# diy-ltcc.net
KiCad netlist of a schematic drawn in EAGLE
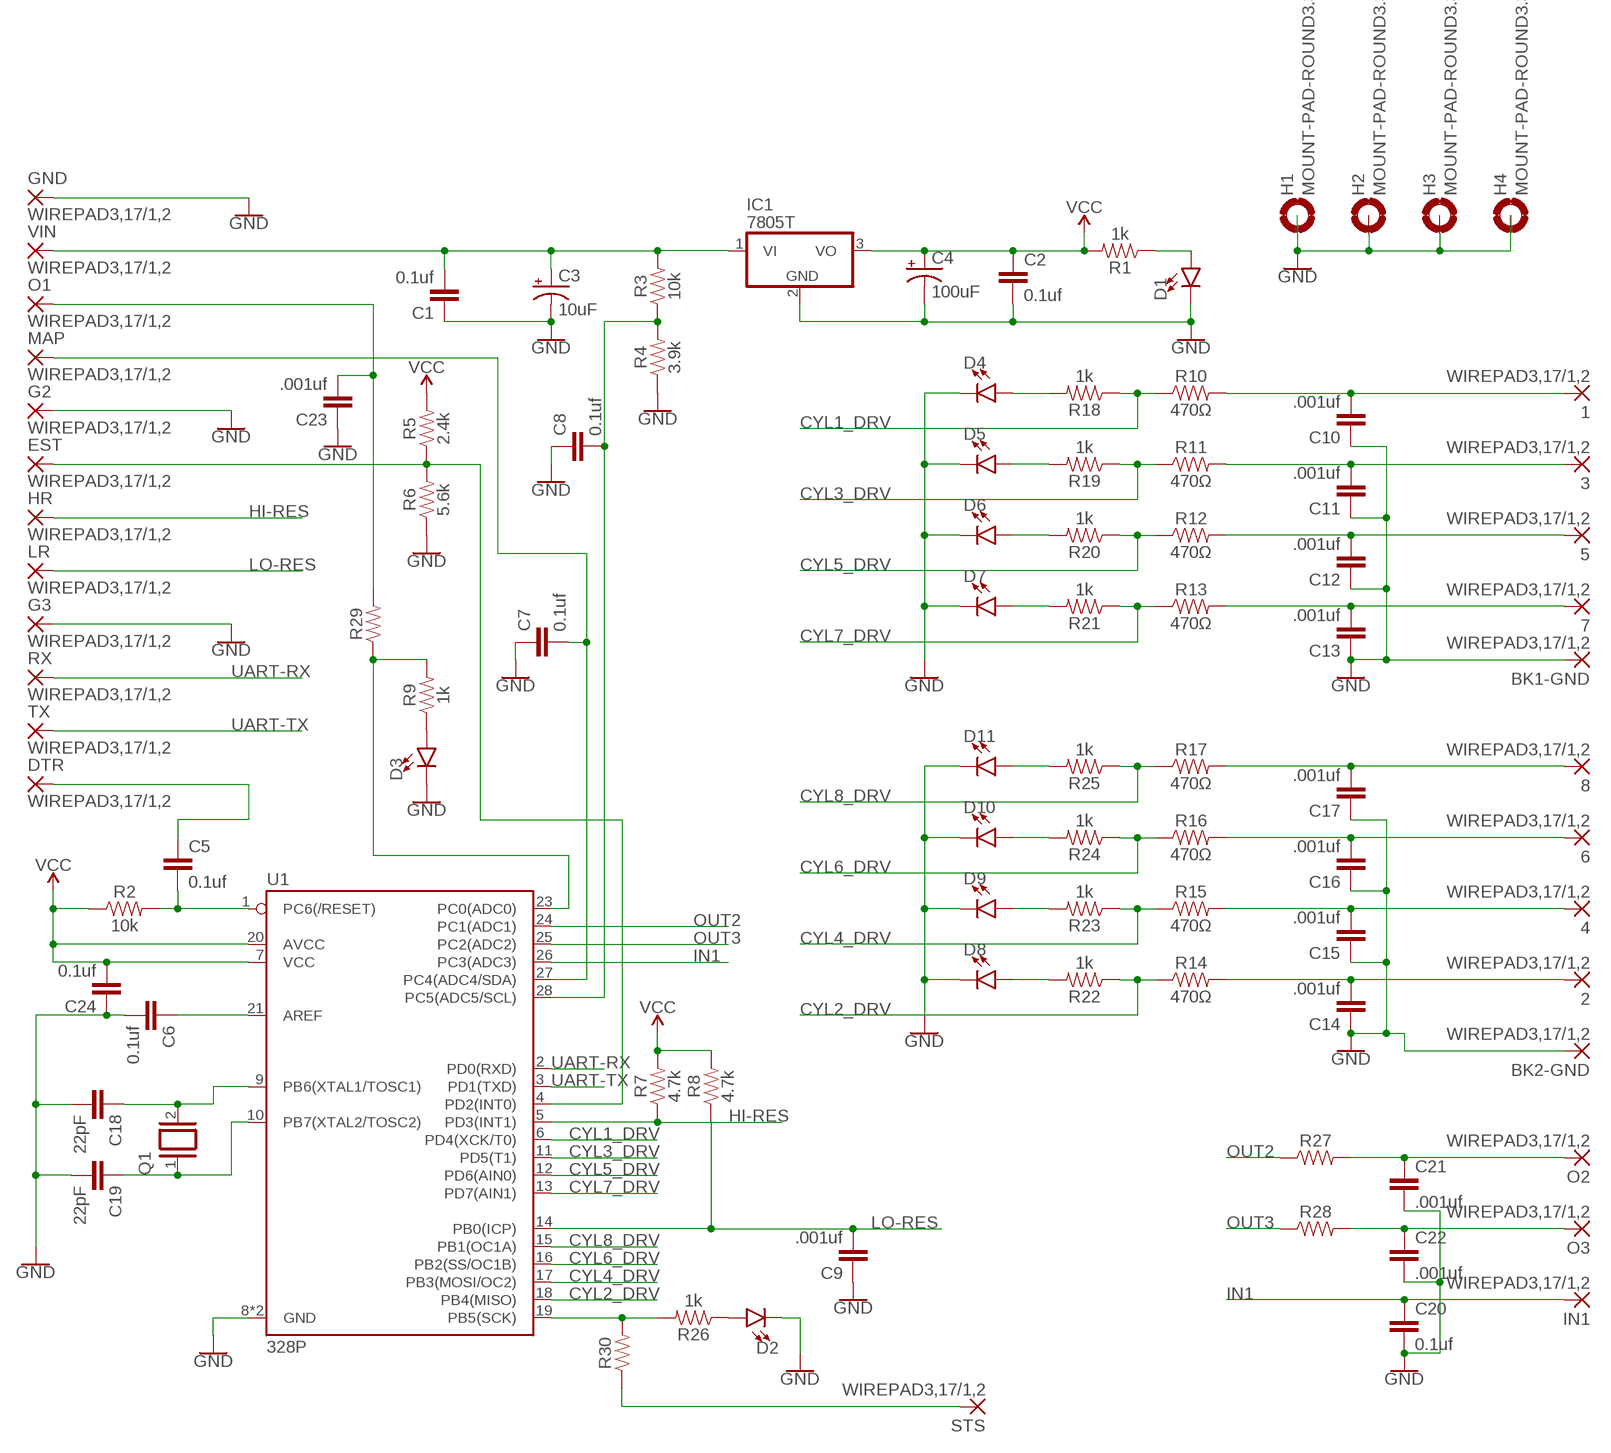
[diagram p0: schematic, sheet 1]

(export (version "E")
  (design (tool "Eeschema 10.0.6"))
  (components
    (comp (ref "1")
      (value "WIREPAD3,17/1,2")
      (footprint "eagle-import:3,17_1,2")
      (libsource (lib "eagle-import") (part "WIREPAD3,17/1,2"))
    )
    (comp (ref "2")
      (value "WIREPAD3,17/1,2")
      (footprint "eagle-import:3,17_1,2")
      (libsource (lib "eagle-import") (part "WIREPAD3,17/1,2"))
    )
    (comp (ref "3")
      (value "WIREPAD3,17/1,2")
      (footprint "eagle-import:3,17_1,2")
      (libsource (lib "eagle-import") (part "WIREPAD3,17/1,2"))
    )
    (comp (ref "4")
      (value "WIREPAD3,17/1,2")
      (footprint "eagle-import:3,17_1,2")
      (libsource (lib "eagle-import") (part "WIREPAD3,17/1,2"))
    )
    (comp (ref "5")
      (value "WIREPAD3,17/1,2")
      (footprint "eagle-import:3,17_1,2")
      (libsource (lib "eagle-import") (part "WIREPAD3,17/1,2"))
    )
    (comp (ref "6")
      (value "WIREPAD3,17/1,2")
      (footprint "eagle-import:3,17_1,2")
      (libsource (lib "eagle-import") (part "WIREPAD3,17/1,2"))
    )
    (comp (ref "7")
      (value "WIREPAD3,17/1,2")
      (footprint "eagle-import:3,17_1,2")
      (libsource (lib "eagle-import") (part "WIREPAD3,17/1,2"))
    )
    (comp (ref "8")
      (value "WIREPAD3,17/1,2")
      (footprint "eagle-import:3,17_1,2")
      (libsource (lib "eagle-import") (part "WIREPAD3,17/1,2"))
    )
    (comp (ref "BK1-GND")
      (value "WIREPAD3,17/1,2")
      (footprint "eagle-import:3,17_1,2")
      (libsource (lib "eagle-import") (part "WIREPAD3,17/1,2"))
    )
    (comp (ref "BK2-GND")
      (value "WIREPAD3,17/1,2")
      (footprint "eagle-import:3,17_1,2")
      (libsource (lib "eagle-import") (part "WIREPAD3,17/1,2"))
    )
    (comp (ref "C1")
      (value "0.1uf")
      (footprint "eagle-import:CAP-PTH-2.54")
      (libsource (lib "eagle-import") (part "22PF-PTH-2.54MM-200V-5%"))
    )
    (comp (ref "C2")
      (value "0.1uf")
      (footprint "eagle-import:CAP-PTH-2.54")
      (libsource (lib "eagle-import") (part "22PF-PTH-2.54MM-200V-5%"))
    )
    (comp (ref "C3")
      (value "10uF")
      (footprint "eagle-import:CPOL-RADIAL-2.5MM-5MM-KIT")
      (libsource (lib "eagle-import") (part "10UF-POLAR-RADIAL-2.5MM-KIT-25V-20%"))
    )
    (comp (ref "C4")
      (value "100uF")
      (footprint "eagle-import:CPOL-RADIAL-2.5MM-6.5MM")
      (libsource (lib "eagle-import") (part "100UF-POLAR-RADIAL-2.5MM-25V-20%"))
    )
    (comp (ref "C5")
      (value "0.1uf")
      (footprint "eagle-import:CAP-PTH-2.54")
      (libsource (lib "eagle-import") (part "22PF-PTH-2.54MM-200V-5%"))
    )
    (comp (ref "C6")
      (value "0.1uf")
      (footprint "eagle-import:CAP-PTH-2.54")
      (libsource (lib "eagle-import") (part "22PF-PTH-2.54MM-200V-5%"))
    )
    (comp (ref "C7")
      (value "0.1uf")
      (footprint "eagle-import:CAP-PTH-2.54")
      (libsource (lib "eagle-import") (part "22PF-PTH-2.54MM-200V-5%"))
    )
    (comp (ref "C8")
      (value "0.1uf")
      (footprint "eagle-import:CAP-PTH-2.54")
      (libsource (lib "eagle-import") (part "22PF-PTH-2.54MM-200V-5%"))
    )
    (comp (ref "C9")
      (value ".001uf")
      (footprint "eagle-import:CAP-PTH-2.54")
      (libsource (lib "eagle-import") (part "22PF-PTH-2.54MM-200V-5%"))
    )
    (comp (ref "C10")
      (value ".001uf")
      (footprint "eagle-import:CAP-PTH-2.54")
      (libsource (lib "eagle-import") (part "22PF-PTH-2.54MM-200V-5%"))
    )
    (comp (ref "C11")
      (value ".001uf")
      (footprint "eagle-import:CAP-PTH-2.54")
      (libsource (lib "eagle-import") (part "22PF-PTH-2.54MM-200V-5%"))
    )
    (comp (ref "C12")
      (value ".001uf")
      (footprint "eagle-import:CAP-PTH-2.54")
      (libsource (lib "eagle-import") (part "22PF-PTH-2.54MM-200V-5%"))
    )
    (comp (ref "C13")
      (value ".001uf")
      (footprint "eagle-import:CAP-PTH-2.54")
      (libsource (lib "eagle-import") (part "22PF-PTH-2.54MM-200V-5%"))
    )
    (comp (ref "C14")
      (value ".001uf")
      (footprint "eagle-import:CAP-PTH-2.54")
      (libsource (lib "eagle-import") (part "22PF-PTH-2.54MM-200V-5%"))
    )
    (comp (ref "C15")
      (value ".001uf")
      (footprint "eagle-import:CAP-PTH-2.54")
      (libsource (lib "eagle-import") (part "22PF-PTH-2.54MM-200V-5%"))
    )
    (comp (ref "C16")
      (value ".001uf")
      (footprint "eagle-import:CAP-PTH-2.54")
      (libsource (lib "eagle-import") (part "22PF-PTH-2.54MM-200V-5%"))
    )
    (comp (ref "C17")
      (value ".001uf")
      (footprint "eagle-import:CAP-PTH-2.54")
      (libsource (lib "eagle-import") (part "22PF-PTH-2.54MM-200V-5%"))
    )
    (comp (ref "C18")
      (value "22pF")
      (footprint "eagle-import:CAP-PTH-2.54")
      (libsource (lib "eagle-import") (part "22PF-PTH-2.54MM-200V-5%"))
    )
    (comp (ref "C19")
      (value "22pF")
      (footprint "eagle-import:CAP-PTH-2.54")
      (libsource (lib "eagle-import") (part "22PF-PTH-2.54MM-200V-5%"))
    )
    (comp (ref "C20")
      (value "0.1uf")
      (footprint "eagle-import:CAP-PTH-2.54")
      (libsource (lib "eagle-import") (part "22PF-PTH-2.54MM-200V-5%"))
    )
    (comp (ref "C21")
      (value ".001uf")
      (footprint "eagle-import:CAP-PTH-2.54")
      (libsource (lib "eagle-import") (part "22PF-PTH-2.54MM-200V-5%"))
    )
    (comp (ref "C22")
      (value ".001uf")
      (footprint "eagle-import:CAP-PTH-2.54")
      (libsource (lib "eagle-import") (part "22PF-PTH-2.54MM-200V-5%"))
    )
    (comp (ref "C23")
      (value ".001uf")
      (footprint "eagle-import:CAP-PTH-2.54")
      (libsource (lib "eagle-import") (part "22PF-PTH-2.54MM-200V-5%"))
    )
    (comp (ref "C24")
      (value "0.1uf")
      (footprint "eagle-import:CAP-PTH-2.54")
      (libsource (lib "eagle-import") (part "22PF-PTH-2.54MM-200V-5%"))
    )
    (comp (ref "D1")
      (value "LED3MM")
      (footprint "eagle-import:LED_3MM")
      (libsource (lib "eagle-import") (part "LED3MM"))
    )
    (comp (ref "D2")
      (value "LED3MM")
      (footprint "eagle-import:LED_3MM")
      (libsource (lib "eagle-import") (part "LED3MM"))
    )
    (comp (ref "D3")
      (value "LED3MM")
      (footprint "eagle-import:LED_3MM")
      (libsource (lib "eagle-import") (part "LED3MM"))
    )
    (comp (ref "D4")
      (value "LED3MM")
      (footprint "eagle-import:LED_3MM")
      (libsource (lib "eagle-import") (part "LED3MM"))
    )
    (comp (ref "D5")
      (value "LED3MM")
      (footprint "eagle-import:LED_3MM")
      (libsource (lib "eagle-import") (part "LED3MM"))
    )
    (comp (ref "D6")
      (value "LED3MM")
      (footprint "eagle-import:LED_3MM")
      (libsource (lib "eagle-import") (part "LED3MM"))
    )
    (comp (ref "D7")
      (value "LED3MM")
      (footprint "eagle-import:LED_3MM")
      (libsource (lib "eagle-import") (part "LED3MM"))
    )
    (comp (ref "D8")
      (value "LED3MM")
      (footprint "eagle-import:LED_3MM")
      (libsource (lib "eagle-import") (part "LED3MM"))
    )
    (comp (ref "D9")
      (value "LED3MM")
      (footprint "eagle-import:LED_3MM")
      (libsource (lib "eagle-import") (part "LED3MM"))
    )
    (comp (ref "D10")
      (value "LED3MM")
      (footprint "eagle-import:LED_3MM")
      (libsource (lib "eagle-import") (part "LED3MM"))
    )
    (comp (ref "D11")
      (value "LED3MM")
      (footprint "eagle-import:LED_3MM")
      (libsource (lib "eagle-import") (part "LED3MM"))
    )
    (comp (ref "DTR")
      (value "WIREPAD3,17/1,2")
      (footprint "eagle-import:3,17_1,2")
      (libsource (lib "eagle-import") (part "WIREPAD3,17/1,2"))
    )
    (comp (ref "EST")
      (value "WIREPAD3,17/1,2")
      (footprint "eagle-import:3,17_1,2")
      (libsource (lib "eagle-import") (part "WIREPAD3,17/1,2"))
    )
    (comp (ref "G2")
      (value "WIREPAD3,17/1,2")
      (footprint "eagle-import:3,17_1,2")
      (libsource (lib "eagle-import") (part "WIREPAD3,17/1,2"))
    )
    (comp (ref "G3")
      (value "WIREPAD3,17/1,2")
      (footprint "eagle-import:3,17_1,2")
      (libsource (lib "eagle-import") (part "WIREPAD3,17/1,2"))
    )
    (comp (ref "GND")
      (value "WIREPAD3,17/1,2")
      (footprint "eagle-import:3,17_1,2")
      (libsource (lib "eagle-import") (part "WIREPAD3,17/1,2"))
    )
    (comp (ref "H1")
      (value "MOUNT-PAD-ROUND3.3")
      (footprint "eagle-import:3,3-PAD")
      (libsource (lib "eagle-import") (part "MOUNT-PAD-ROUND3.3"))
    )
    (comp (ref "H2")
      (value "MOUNT-PAD-ROUND3.3")
      (footprint "eagle-import:3,3-PAD")
      (libsource (lib "eagle-import") (part "MOUNT-PAD-ROUND3.3"))
    )
    (comp (ref "H3")
      (value "MOUNT-PAD-ROUND3.3")
      (footprint "eagle-import:3,3-PAD")
      (libsource (lib "eagle-import") (part "MOUNT-PAD-ROUND3.3"))
    )
    (comp (ref "H4")
      (value "MOUNT-PAD-ROUND3.3")
      (footprint "eagle-import:3,3-PAD")
      (libsource (lib "eagle-import") (part "MOUNT-PAD-ROUND3.3"))
    )
    (comp (ref "HR")
      (value "WIREPAD3,17/1,2")
      (footprint "eagle-import:3,17_1,2")
      (libsource (lib "eagle-import") (part "WIREPAD3,17/1,2"))
    )
    (comp (ref "IC1")
      (value "7805T")
      (footprint "eagle-import:TO220H")
      (libsource (lib "eagle-import") (part "78T05"))
    )
    (comp (ref "IN1")
      (value "WIREPAD3,17/1,2")
      (footprint "eagle-import:3,17_1,2")
      (libsource (lib "eagle-import") (part "WIREPAD3,17/1,2"))
    )
    (comp (ref "LR")
      (value "WIREPAD3,17/1,2")
      (footprint "eagle-import:3,17_1,2")
      (libsource (lib "eagle-import") (part "WIREPAD3,17/1,2"))
    )
    (comp (ref "MAP")
      (value "WIREPAD3,17/1,2")
      (footprint "eagle-import:3,17_1,2")
      (libsource (lib "eagle-import") (part "WIREPAD3,17/1,2"))
    )
    (comp (ref "O1")
      (value "WIREPAD3,17/1,2")
      (footprint "eagle-import:3,17_1,2")
      (libsource (lib "eagle-import") (part "WIREPAD3,17/1,2"))
    )
    (comp (ref "O2")
      (value "WIREPAD3,17/1,2")
      (footprint "eagle-import:3,17_1,2")
      (libsource (lib "eagle-import") (part "WIREPAD3,17/1,2"))
    )
    (comp (ref "O3")
      (value "WIREPAD3,17/1,2")
      (footprint "eagle-import:3,17_1,2")
      (libsource (lib "eagle-import") (part "WIREPAD3,17/1,2"))
    )
    (comp (ref "Q1")
      (value "XTAL/S")
      (footprint "eagle-import:QS")
      (libsource (lib "eagle-import") (part "XTAL/S"))
    )
    (comp (ref "R1")
      (value "1k")
      (footprint "eagle-import:AXIAL-0.3")
      (libsource (lib "eagle-import") (part "1KOHM-HORIZ-1/4W-5%"))
    )
    (comp (ref "R2")
      (value "10k")
      (footprint "eagle-import:AXIAL-0.3")
      (libsource (lib "eagle-import") (part "10KOHM-HORIZ-1/4W-5%"))
    )
    (comp (ref "R3")
      (value "10k")
      (footprint "eagle-import:AXIAL-0.3")
      (libsource (lib "eagle-import") (part "10KOHM-HORIZ-1/4W-5%"))
    )
    (comp (ref "R4")
      (value "3.9k")
      (footprint "eagle-import:AXIAL-0.3")
      (libsource (lib "eagle-import") (part "10KOHM-HORIZ-1/4W-5%"))
    )
    (comp (ref "R5")
      (value "2.4k")
      (footprint "eagle-import:AXIAL-0.3")
      (libsource (lib "eagle-import") (part "1KOHM-HORIZ-1/4W-1%"))
    )
    (comp (ref "R6")
      (value "5.6k")
      (footprint "eagle-import:AXIAL-0.3")
      (libsource (lib "eagle-import") (part "1KOHM-HORIZ-1/4W-1%"))
    )
    (comp (ref "R7")
      (value "4.7k")
      (footprint "eagle-import:AXIAL-0.3")
      (libsource (lib "eagle-import") (part "10KOHM-HORIZ-1/4W-5%"))
    )
    (comp (ref "R8")
      (value "4.7k")
      (footprint "eagle-import:AXIAL-0.3")
      (libsource (lib "eagle-import") (part "10KOHM-HORIZ-1/4W-5%"))
    )
    (comp (ref "R9")
      (value "1k")
      (footprint "eagle-import:AXIAL-0.3")
      (libsource (lib "eagle-import") (part "1KOHM-HORIZ-1/4W-1%"))
    )
    (comp (ref "R10")
      (value "470Ω")
      (footprint "eagle-import:AXIAL-0.3")
      (libsource (lib "eagle-import") (part "1KOHM-HORIZ-1/4W-1%"))
    )
    (comp (ref "R11")
      (value "470Ω")
      (footprint "eagle-import:AXIAL-0.3")
      (libsource (lib "eagle-import") (part "1KOHM-HORIZ-1/4W-1%"))
    )
    (comp (ref "R12")
      (value "470Ω")
      (footprint "eagle-import:AXIAL-0.3")
      (libsource (lib "eagle-import") (part "1KOHM-HORIZ-1/4W-1%"))
    )
    (comp (ref "R13")
      (value "470Ω")
      (footprint "eagle-import:AXIAL-0.3")
      (libsource (lib "eagle-import") (part "1KOHM-HORIZ-1/4W-1%"))
    )
    (comp (ref "R14")
      (value "470Ω")
      (footprint "eagle-import:AXIAL-0.3")
      (libsource (lib "eagle-import") (part "1KOHM-HORIZ-1/4W-1%"))
    )
    (comp (ref "R15")
      (value "470Ω")
      (footprint "eagle-import:AXIAL-0.3")
      (libsource (lib "eagle-import") (part "1KOHM-HORIZ-1/4W-1%"))
    )
    (comp (ref "R16")
      (value "470Ω")
      (footprint "eagle-import:AXIAL-0.3")
      (libsource (lib "eagle-import") (part "1KOHM-HORIZ-1/4W-1%"))
    )
    (comp (ref "R17")
      (value "470Ω")
      (footprint "eagle-import:AXIAL-0.3")
      (libsource (lib "eagle-import") (part "1KOHM-HORIZ-1/4W-1%"))
    )
    (comp (ref "R18")
      (value "1k")
      (footprint "eagle-import:AXIAL-0.3")
      (libsource (lib "eagle-import") (part "1KOHM-HORIZ-1/4W-1%"))
    )
    (comp (ref "R19")
      (value "1k")
      (footprint "eagle-import:AXIAL-0.3")
      (libsource (lib "eagle-import") (part "1KOHM-HORIZ-1/4W-1%"))
    )
    (comp (ref "R20")
      (value "1k")
      (footprint "eagle-import:AXIAL-0.3")
      (libsource (lib "eagle-import") (part "1KOHM-HORIZ-1/4W-1%"))
    )
    (comp (ref "R21")
      (value "1k")
      (footprint "eagle-import:AXIAL-0.3")
      (libsource (lib "eagle-import") (part "1KOHM-HORIZ-1/4W-1%"))
    )
    (comp (ref "R22")
      (value "1k")
      (footprint "eagle-import:AXIAL-0.3")
      (libsource (lib "eagle-import") (part "1KOHM-HORIZ-1/4W-1%"))
    )
    (comp (ref "R23")
      (value "1k")
      (footprint "eagle-import:AXIAL-0.3")
      (libsource (lib "eagle-import") (part "1KOHM-HORIZ-1/4W-1%"))
    )
    (comp (ref "R24")
      (value "1k")
      (footprint "eagle-import:AXIAL-0.3")
      (libsource (lib "eagle-import") (part "1KOHM-HORIZ-1/4W-1%"))
    )
    (comp (ref "R25")
      (value "1k")
      (footprint "eagle-import:AXIAL-0.3")
      (libsource (lib "eagle-import") (part "1KOHM-HORIZ-1/4W-1%"))
    )
    (comp (ref "R26")
      (value "1k")
      (footprint "eagle-import:AXIAL-0.3")
      (libsource (lib "eagle-import") (part "1KOHM-HORIZ-1/4W-1%"))
    )
    (comp (ref "R27")
      (value "1KOHM-HORIZ-1/4W-1%")
      (footprint "eagle-import:AXIAL-0.3")
      (libsource (lib "eagle-import") (part "1KOHM-HORIZ-1/4W-1%"))
    )
    (comp (ref "R28")
      (value "1KOHM-HORIZ-1/4W-1%")
      (footprint "eagle-import:AXIAL-0.3")
      (libsource (lib "eagle-import") (part "1KOHM-HORIZ-1/4W-1%"))
    )
    (comp (ref "R29")
      (value "1KOHM-HORIZ-1/4W-1%")
      (footprint "eagle-import:AXIAL-0.3")
      (libsource (lib "eagle-import") (part "1KOHM-HORIZ-1/4W-1%"))
    )
    (comp (ref "R30")
      (value "1KOHM-HORIZ-1/4W-1%")
      (footprint "eagle-import:AXIAL-0.3")
      (libsource (lib "eagle-import") (part "1KOHM-HORIZ-1/4W-1%"))
    )
    (comp (ref "RX")
      (value "WIREPAD3,17/1,2")
      (footprint "eagle-import:3,17_1,2")
      (libsource (lib "eagle-import") (part "WIREPAD3,17/1,2"))
    )
    (comp (ref "STS")
      (value "WIREPAD3,17/1,2")
      (footprint "eagle-import:3,17_1,2")
      (libsource (lib "eagle-import") (part "WIREPAD3,17/1,2"))
    )
    (comp (ref "TX")
      (value "WIREPAD3,17/1,2")
      (footprint "eagle-import:3,17_1,2")
      (libsource (lib "eagle-import") (part "WIREPAD3,17/1,2"))
    )
    (comp (ref "U1")
      (value "328P")
      (footprint "eagle-import:DIP28")
      (libsource (lib "eagle-import") (part "ATMEGA328P_PDIP"))
    )
    (comp (ref "VIN")
      (value "WIREPAD3,17/1,2")
      (footprint "eagle-import:3,17_1,2")
      (libsource (lib "eagle-import") (part "WIREPAD3,17/1,2"))
    )
  )
  (nets
    (net (code "1") (name "/CYL1_DRV") (class "Default")
      (node (ref "R10") (pin "P$1") (pinfunction "1_P$1") (pintype "passive"))
      (node (ref "R18") (pin "P$1") (pinfunction "1_P$1") (pintype "passive"))
      (node (ref "U1") (pin "6") (pinfunction "PD4(XCK/T0)_6") (pintype "bidirectional"))
    )
    (net (code "2") (name "/CYL2_DRV") (class "Default")
      (node (ref "R14") (pin "P$1") (pinfunction "1_P$1") (pintype "passive"))
      (node (ref "R22") (pin "P$1") (pinfunction "1_P$1") (pintype "passive"))
      (node (ref "U1") (pin "18") (pinfunction "PB4(MISO)_18") (pintype "bidirectional"))
    )
    (net (code "3") (name "/CYL3_DRV") (class "Default")
      (node (ref "R11") (pin "P$1") (pinfunction "1_P$1") (pintype "passive"))
      (node (ref "R19") (pin "P$1") (pinfunction "1_P$1") (pintype "passive"))
      (node (ref "U1") (pin "11") (pinfunction "PD5(T1)_11") (pintype "bidirectional"))
    )
    (net (code "4") (name "/CYL4_DRV") (class "Default")
      (node (ref "R15") (pin "P$1") (pinfunction "1_P$1") (pintype "passive"))
      (node (ref "R23") (pin "P$1") (pinfunction "1_P$1") (pintype "passive"))
      (node (ref "U1") (pin "17") (pinfunction "PB3(MOSI/OC2)_17") (pintype "bidirectional"))
    )
    (net (code "5") (name "/CYL5_DRV") (class "Default")
      (node (ref "R12") (pin "P$1") (pinfunction "1_P$1") (pintype "passive"))
      (node (ref "R20") (pin "P$1") (pinfunction "1_P$1") (pintype "passive"))
      (node (ref "U1") (pin "12") (pinfunction "PD6(AIN0)_12") (pintype "bidirectional"))
    )
    (net (code "6") (name "/CYL6_DRV") (class "Default")
      (node (ref "R16") (pin "P$1") (pinfunction "1_P$1") (pintype "passive"))
      (node (ref "R24") (pin "P$1") (pinfunction "1_P$1") (pintype "passive"))
      (node (ref "U1") (pin "16") (pinfunction "PB2(SS/OC1B)_16") (pintype "bidirectional"))
    )
    (net (code "7") (name "/CYL7_DRV") (class "Default")
      (node (ref "R13") (pin "P$1") (pinfunction "1_P$1") (pintype "passive"))
      (node (ref "R21") (pin "P$1") (pinfunction "1_P$1") (pintype "passive"))
      (node (ref "U1") (pin "13") (pinfunction "PD7(AIN1)_13") (pintype "bidirectional"))
    )
    (net (code "8") (name "/CYL8_DRV") (class "Default")
      (node (ref "R17") (pin "P$1") (pinfunction "1_P$1") (pintype "passive"))
      (node (ref "R25") (pin "P$1") (pinfunction "1_P$1") (pintype "passive"))
      (node (ref "U1") (pin "15") (pinfunction "PB1(OC1A)_15") (pintype "bidirectional"))
    )
    (net (code "9") (name "/HI-RES") (class "Default")
      (node (ref "HR") (pin "1") (pinfunction "P_1") (pintype "passive"))
      (node (ref "R7") (pin "P$1") (pinfunction "1_P$1") (pintype "passive"))
      (node (ref "U1") (pin "5") (pinfunction "PD3(INT1)_5") (pintype "bidirectional"))
    )
    (net (code "10") (name "/IN1") (class "Default")
      (node (ref "C20") (pin "1") (pinfunction "1_1") (pintype "passive"))
      (node (ref "IN1") (pin "1") (pinfunction "P_1") (pintype "passive"))
      (node (ref "U1") (pin "26") (pinfunction "PC3(ADC3)_26") (pintype "bidirectional"))
    )
    (net (code "11") (name "/LO-RES") (class "Default")
      (node (ref "C9") (pin "2") (pinfunction "2_2") (pintype "passive"))
      (node (ref "LR") (pin "1") (pinfunction "P_1") (pintype "passive"))
      (node (ref "R8") (pin "P$1") (pinfunction "1_P$1") (pintype "passive"))
      (node (ref "U1") (pin "14") (pinfunction "PB0(ICP)_14") (pintype "bidirectional"))
    )
    (net (code "12") (name "/OUT2") (class "Default")
      (node (ref "R27") (pin "P$1") (pinfunction "1_P$1") (pintype "passive"))
      (node (ref "U1") (pin "24") (pinfunction "PC1(ADC1)_24") (pintype "bidirectional"))
    )
    (net (code "13") (name "/OUT3") (class "Default")
      (node (ref "R28") (pin "P$1") (pinfunction "1_P$1") (pintype "passive"))
      (node (ref "U1") (pin "25") (pinfunction "PC2(ADC2)_25") (pintype "bidirectional"))
    )
    (net (code "14") (name "/UART-RX") (class "Default")
      (node (ref "RX") (pin "1") (pinfunction "P_1") (pintype "passive"))
      (node (ref "U1") (pin "2") (pinfunction "PD0(RXD)_2") (pintype "bidirectional"))
    )
    (net (code "15") (name "/UART-TX") (class "Default")
      (node (ref "TX") (pin "1") (pinfunction "P_1") (pintype "passive"))
      (node (ref "U1") (pin "3") (pinfunction "PD1(TXD)_3") (pintype "bidirectional"))
    )
    (net (code "16") (name "GND") (class "Default")
      (node (ref "BK1-GND") (pin "1") (pinfunction "P_1") (pintype "passive"))
      (node (ref "BK2-GND") (pin "1") (pinfunction "P_1") (pintype "passive"))
      (node (ref "C1") (pin "1") (pinfunction "1_1") (pintype "passive"))
      (node (ref "C10") (pin "1") (pinfunction "1_1") (pintype "passive"))
      (node (ref "C11") (pin "1") (pinfunction "1_1") (pintype "passive"))
      (node (ref "C12") (pin "1") (pinfunction "1_1") (pintype "passive"))
      (node (ref "C13") (pin "1") (pinfunction "1_1") (pintype "passive"))
      (node (ref "C14") (pin "1") (pinfunction "1_1") (pintype "passive"))
      (node (ref "C15") (pin "1") (pinfunction "1_1") (pintype "passive"))
      (node (ref "C16") (pin "1") (pinfunction "1_1") (pintype "passive"))
      (node (ref "C17") (pin "1") (pinfunction "1_1") (pintype "passive"))
      (node (ref "C18") (pin "2") (pinfunction "2_2") (pintype "passive"))
      (node (ref "C19") (pin "2") (pinfunction "2_2") (pintype "passive"))
      (node (ref "C2") (pin "2") (pinfunction "2_2") (pintype "passive"))
      (node (ref "C20") (pin "2") (pinfunction "2_2") (pintype "passive"))
      (node (ref "C21") (pin "2") (pinfunction "2_2") (pintype "passive"))
      (node (ref "C22") (pin "2") (pinfunction "2_2") (pintype "passive"))
      (node (ref "C23") (pin "1") (pinfunction "1_1") (pintype "passive"))
      (node (ref "C24") (pin "1") (pinfunction "1_1") (pintype "passive"))
      (node (ref "C3") (pin "2") (pinfunction "-_2") (pintype "passive"))
      (node (ref "C4") (pin "2") (pinfunction "-_2") (pintype "passive"))
      (node (ref "C6") (pin "2") (pinfunction "2_2") (pintype "passive"))
      (node (ref "C7") (pin "1") (pinfunction "1_1") (pintype "passive"))
      (node (ref "C8") (pin "1") (pinfunction "1_1") (pintype "passive"))
      (node (ref "C9") (pin "1") (pinfunction "1_1") (pintype "passive"))
      (node (ref "D1") (pin "K") (pinfunction "C_K") (pintype "passive"))
      (node (ref "D10") (pin "K") (pinfunction "C_K") (pintype "passive"))
      (node (ref "D11") (pin "K") (pinfunction "C_K") (pintype "passive"))
      (node (ref "D2") (pin "K") (pinfunction "C_K") (pintype "passive"))
      (node (ref "D3") (pin "K") (pinfunction "C_K") (pintype "passive"))
      (node (ref "D4") (pin "K") (pinfunction "C_K") (pintype "passive"))
      (node (ref "D5") (pin "K") (pinfunction "C_K") (pintype "passive"))
      (node (ref "D6") (pin "K") (pinfunction "C_K") (pintype "passive"))
      (node (ref "D7") (pin "K") (pinfunction "C_K") (pintype "passive"))
      (node (ref "D8") (pin "K") (pinfunction "C_K") (pintype "passive"))
      (node (ref "D9") (pin "K") (pinfunction "C_K") (pintype "passive"))
      (node (ref "G2") (pin "1") (pinfunction "P_1") (pintype "passive"))
      (node (ref "G3") (pin "1") (pinfunction "P_1") (pintype "passive"))
      (node (ref "GND") (pin "1") (pinfunction "P_1") (pintype "passive"))
      (node (ref "H1") (pin "B3,3") (pinfunction "MOUNT_B3,3") (pintype "passive"))
      (node (ref "H2") (pin "B3,3") (pinfunction "MOUNT_B3,3") (pintype "passive"))
      (node (ref "H3") (pin "B3,3") (pinfunction "MOUNT_B3,3") (pintype "passive"))
      (node (ref "H4") (pin "B3,3") (pinfunction "MOUNT_B3,3") (pintype "passive"))
      (node (ref "IC1") (pin "2") (pinfunction "GND_2") (pintype "passive"))
      (node (ref "R4") (pin "P$1") (pinfunction "1_P$1") (pintype "passive"))
      (node (ref "R6") (pin "P$1") (pinfunction "1_P$1") (pintype "passive"))
      (node (ref "U1") (pin "22") (pinfunction "GND_22") (pintype "bidirectional"))
      (node (ref "U1") (pin "8") (pinfunction "GND_8") (pintype "bidirectional"))
    )
    (net (code "17") (name "Net-(1-P)") (class "Default")
      (node (ref "1") (pin "1") (pinfunction "P_1") (pintype "passive"))
      (node (ref "C10") (pin "2") (pinfunction "2_2") (pintype "passive"))
      (node (ref "R10") (pin "P$2") (pinfunction "2_P$2") (pintype "passive"))
    )
    (net (code "18") (name "Net-(2-P)") (class "Default")
      (node (ref "2") (pin "1") (pinfunction "P_1") (pintype "passive"))
      (node (ref "C14") (pin "2") (pinfunction "2_2") (pintype "passive"))
      (node (ref "R14") (pin "P$2") (pinfunction "2_P$2") (pintype "passive"))
    )
    (net (code "19") (name "Net-(3-P)") (class "Default")
      (node (ref "3") (pin "1") (pinfunction "P_1") (pintype "passive"))
      (node (ref "C11") (pin "2") (pinfunction "2_2") (pintype "passive"))
      (node (ref "R11") (pin "P$2") (pinfunction "2_P$2") (pintype "passive"))
    )
    (net (code "20") (name "Net-(4-P)") (class "Default")
      (node (ref "4") (pin "1") (pinfunction "P_1") (pintype "passive"))
      (node (ref "C15") (pin "2") (pinfunction "2_2") (pintype "passive"))
      (node (ref "R15") (pin "P$2") (pinfunction "2_P$2") (pintype "passive"))
    )
    (net (code "21") (name "Net-(5-P)") (class "Default")
      (node (ref "5") (pin "1") (pinfunction "P_1") (pintype "passive"))
      (node (ref "C12") (pin "2") (pinfunction "2_2") (pintype "passive"))
      (node (ref "R12") (pin "P$2") (pinfunction "2_P$2") (pintype "passive"))
    )
    (net (code "22") (name "Net-(6-P)") (class "Default")
      (node (ref "6") (pin "1") (pinfunction "P_1") (pintype "passive"))
      (node (ref "C16") (pin "2") (pinfunction "2_2") (pintype "passive"))
      (node (ref "R16") (pin "P$2") (pinfunction "2_P$2") (pintype "passive"))
    )
    (net (code "23") (name "Net-(7-P)") (class "Default")
      (node (ref "7") (pin "1") (pinfunction "P_1") (pintype "passive"))
      (node (ref "C13") (pin "2") (pinfunction "2_2") (pintype "passive"))
      (node (ref "R13") (pin "P$2") (pinfunction "2_P$2") (pintype "passive"))
    )
    (net (code "24") (name "Net-(8-P)") (class "Default")
      (node (ref "8") (pin "1") (pinfunction "P_1") (pintype "passive"))
      (node (ref "C17") (pin "2") (pinfunction "2_2") (pintype "passive"))
      (node (ref "R17") (pin "P$2") (pinfunction "2_P$2") (pintype "passive"))
    )
    (net (code "25") (name "Net-(C3-+)") (class "Default")
      (node (ref "C1") (pin "2") (pinfunction "2_2") (pintype "passive"))
      (node (ref "C3") (pin "1") (pinfunction "+_1") (pintype "passive"))
      (node (ref "IC1") (pin "1") (pinfunction "VI_1") (pintype "input"))
      (node (ref "R3") (pin "P$2") (pinfunction "2_P$2") (pintype "passive"))
      (node (ref "VIN") (pin "1") (pinfunction "P_1") (pintype "passive"))
    )
    (net (code "26") (name "Net-(DTR-P)") (class "Default")
      (node (ref "C5") (pin "1") (pinfunction "1_1") (pintype "passive"))
      (node (ref "DTR") (pin "1") (pinfunction "P_1") (pintype "passive"))
    )
    (net (code "27") (name "Net-(EST-P)") (class "Default")
      (node (ref "EST") (pin "1") (pinfunction "P_1") (pintype "passive"))
      (node (ref "R5") (pin "P$1") (pinfunction "1_P$1") (pintype "passive"))
      (node (ref "R6") (pin "P$2") (pinfunction "2_P$2") (pintype "passive"))
      (node (ref "U1") (pin "4") (pinfunction "PD2(INT0)_4") (pintype "bidirectional"))
    )
    (net (code "28") (name "Net-(MAP-P)") (class "Default")
      (node (ref "C7") (pin "2") (pinfunction "2_2") (pintype "passive"))
      (node (ref "MAP") (pin "1") (pinfunction "P_1") (pintype "passive"))
      (node (ref "U1") (pin "27") (pinfunction "PC4(ADC4/SDA)_27") (pintype "bidirectional"))
    )
    (net (code "29") (name "Net-(O1-P)") (class "Default")
      (node (ref "C23") (pin "2") (pinfunction "2_2") (pintype "passive"))
      (node (ref "O1") (pin "1") (pinfunction "P_1") (pintype "passive"))
      (node (ref "R29") (pin "P$2") (pinfunction "2_P$2") (pintype "passive"))
    )
    (net (code "30") (name "Net-(O2-P)") (class "Default")
      (node (ref "C21") (pin "1") (pinfunction "1_1") (pintype "passive"))
      (node (ref "O2") (pin "1") (pinfunction "P_1") (pintype "passive"))
      (node (ref "R27") (pin "P$2") (pinfunction "2_P$2") (pintype "passive"))
    )
    (net (code "31") (name "Net-(O3-P)") (class "Default")
      (node (ref "C22") (pin "1") (pinfunction "1_1") (pintype "passive"))
      (node (ref "O3") (pin "1") (pinfunction "P_1") (pintype "passive"))
      (node (ref "R28") (pin "P$2") (pinfunction "2_P$2") (pintype "passive"))
    )
    (net (code "32") (name "Net-(R1-1)") (class "Default")
      (node (ref "D1") (pin "A") (pinfunction "A_A") (pintype "passive"))
      (node (ref "R1") (pin "P$1") (pinfunction "1_P$1") (pintype "passive"))
    )
    (net (code "33") (name "Net-(R2-2)") (class "Default")
      (node (ref "C5") (pin "2") (pinfunction "2_2") (pintype "passive"))
      (node (ref "R2") (pin "P$2") (pinfunction "2_P$2") (pintype "passive"))
      (node (ref "U1") (pin "1") (pinfunction "PC6(/RESET)_1") (pintype "bidirectional"))
    )
    (net (code "34") (name "Net-(R3-1)") (class "Default")
      (node (ref "C8") (pin "2") (pinfunction "2_2") (pintype "passive"))
      (node (ref "R3") (pin "P$1") (pinfunction "1_P$1") (pintype "passive"))
      (node (ref "R4") (pin "P$2") (pinfunction "2_P$2") (pintype "passive"))
      (node (ref "U1") (pin "28") (pinfunction "PC5(ADC5/SCL)_28") (pintype "bidirectional"))
    )
    (net (code "35") (name "Net-(R9-1)") (class "Default")
      (node (ref "D3") (pin "A") (pinfunction "A_A") (pintype "passive"))
      (node (ref "R9") (pin "P$1") (pinfunction "1_P$1") (pintype "passive"))
    )
    (net (code "36") (name "Net-(R18-2)") (class "Default")
      (node (ref "D4") (pin "A") (pinfunction "A_A") (pintype "passive"))
      (node (ref "R18") (pin "P$2") (pinfunction "2_P$2") (pintype "passive"))
    )
    (net (code "37") (name "Net-(R19-2)") (class "Default")
      (node (ref "D5") (pin "A") (pinfunction "A_A") (pintype "passive"))
      (node (ref "R19") (pin "P$2") (pinfunction "2_P$2") (pintype "passive"))
    )
    (net (code "38") (name "Net-(R20-2)") (class "Default")
      (node (ref "D6") (pin "A") (pinfunction "A_A") (pintype "passive"))
      (node (ref "R20") (pin "P$2") (pinfunction "2_P$2") (pintype "passive"))
    )
    (net (code "39") (name "Net-(R21-2)") (class "Default")
      (node (ref "D7") (pin "A") (pinfunction "A_A") (pintype "passive"))
      (node (ref "R21") (pin "P$2") (pinfunction "2_P$2") (pintype "passive"))
    )
    (net (code "40") (name "Net-(R22-2)") (class "Default")
      (node (ref "D8") (pin "A") (pinfunction "A_A") (pintype "passive"))
      (node (ref "R22") (pin "P$2") (pinfunction "2_P$2") (pintype "passive"))
    )
    (net (code "41") (name "Net-(R23-2)") (class "Default")
      (node (ref "D9") (pin "A") (pinfunction "A_A") (pintype "passive"))
      (node (ref "R23") (pin "P$2") (pinfunction "2_P$2") (pintype "passive"))
    )
    (net (code "42") (name "Net-(R24-2)") (class "Default")
      (node (ref "D10") (pin "A") (pinfunction "A_A") (pintype "passive"))
      (node (ref "R24") (pin "P$2") (pinfunction "2_P$2") (pintype "passive"))
    )
    (net (code "43") (name "Net-(R25-2)") (class "Default")
      (node (ref "D11") (pin "A") (pinfunction "A_A") (pintype "passive"))
      (node (ref "R25") (pin "P$2") (pinfunction "2_P$2") (pintype "passive"))
    )
    (net (code "44") (name "Net-(R26-1)") (class "Default")
      (node (ref "D2") (pin "A") (pinfunction "A_A") (pintype "passive"))
      (node (ref "R26") (pin "P$1") (pinfunction "1_P$1") (pintype "passive"))
    )
    (net (code "45") (name "Net-(R26-2)") (class "Default")
      (node (ref "R26") (pin "P$2") (pinfunction "2_P$2") (pintype "passive"))
      (node (ref "R30") (pin "P$2") (pinfunction "2_P$2") (pintype "passive"))
      (node (ref "U1") (pin "19") (pinfunction "PB5(SCK)_19") (pintype "bidirectional"))
    )
    (net (code "46") (name "Net-(R29-1)") (class "Default")
      (node (ref "R29") (pin "P$1") (pinfunction "1_P$1") (pintype "passive"))
      (node (ref "R9") (pin "P$2") (pinfunction "2_P$2") (pintype "passive"))
      (node (ref "U1") (pin "23") (pinfunction "PC0(ADC0)_23") (pintype "bidirectional"))
    )
    (net (code "47") (name "Net-(R30-1)") (class "Default")
      (node (ref "R30") (pin "P$1") (pinfunction "1_P$1") (pintype "passive"))
      (node (ref "STS") (pin "1") (pinfunction "P_1") (pintype "passive"))
    )
    (net (code "48") (name "Net-(U1-AREF)") (class "Default")
      (node (ref "C6") (pin "1") (pinfunction "1_1") (pintype "passive"))
      (node (ref "U1") (pin "21") (pinfunction "AREF_21") (pintype "bidirectional"))
    )
    (net (code "49") (name "Net-(U1-PB6(XTAL1{slash}TOSC1))") (class "Default")
      (node (ref "C18") (pin "1") (pinfunction "1_1") (pintype "passive"))
      (node (ref "Q1") (pin "2") (pinfunction "2_2") (pintype "passive"))
      (node (ref "U1") (pin "9") (pinfunction "PB6(XTAL1/TOSC1)_9") (pintype "bidirectional"))
    )
    (net (code "50") (name "Net-(U1-PB7(XTAL2{slash}TOSC2))") (class "Default")
      (node (ref "C19") (pin "1") (pinfunction "1_1") (pintype "passive"))
      (node (ref "Q1") (pin "1") (pinfunction "1_1") (pintype "passive"))
      (node (ref "U1") (pin "10") (pinfunction "PB7(XTAL2/TOSC2)_10") (pintype "bidirectional"))
    )
    (net (code "51") (name "VCC") (class "Default")
      (node (ref "C2") (pin "1") (pinfunction "1_1") (pintype "passive"))
      (node (ref "C24") (pin "2") (pinfunction "2_2") (pintype "passive"))
      (node (ref "C4") (pin "1") (pinfunction "+_1") (pintype "passive"))
      (node (ref "IC1") (pin "3") (pinfunction "VO_3") (pintype "passive"))
      (node (ref "R1") (pin "P$2") (pinfunction "2_P$2") (pintype "passive"))
      (node (ref "R2") (pin "P$1") (pinfunction "1_P$1") (pintype "passive"))
      (node (ref "R5") (pin "P$2") (pinfunction "2_P$2") (pintype "passive"))
      (node (ref "R7") (pin "P$2") (pinfunction "2_P$2") (pintype "passive"))
      (node (ref "R8") (pin "P$2") (pinfunction "2_P$2") (pintype "passive"))
      (node (ref "U1") (pin "20") (pinfunction "AVCC_20") (pintype "bidirectional"))
      (node (ref "U1") (pin "7") (pinfunction "VCC_7") (pintype "bidirectional"))
    )
  )
)
